# motor.net
KiCad netlist of a schematic drawn in Altium Designer
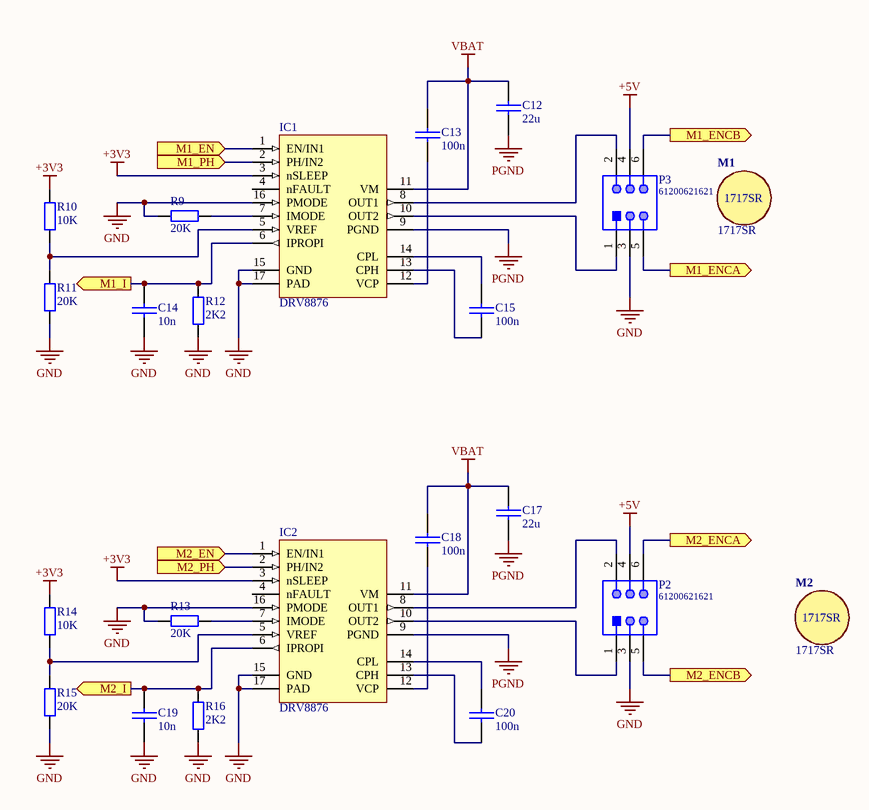
[diagram p0: motor.SchDoc]

(export (version "E")
  (design (tool "Eeschema 10.0.6"))
  (components
    (comp (ref "C12")
      (value "22u")
      (footprint "C0603_PASTE")
      (description "Multilayer Ceramic Capacitors MLCC - SMD 0603")
      (libsource (lib "Passives") (part "C-0603"))
    )
    (comp (ref "C13")
      (value "100n")
      (footprint "C0402-Paste")
      (description "Multilayer Ceramic Capacitors MLCC - SMD  0402")
      (libsource (lib "Passives") (part "C-0402"))
    )
    (comp (ref "C14")
      (value "10n")
      (footprint "C0402-Paste")
      (description "Multilayer Ceramic Capacitors MLCC - SMD  0402")
      (libsource (lib "Passives") (part "C-0402"))
    )
    (comp (ref "C15")
      (value "100n")
      (footprint "C0402-Paste")
      (description "Multilayer Ceramic Capacitors MLCC - SMD  0402")
      (libsource (lib "Passives") (part "C-0402"))
    )
    (comp (ref "C17")
      (value "22u")
      (footprint "C0603_PASTE")
      (description "Multilayer Ceramic Capacitors MLCC - SMD 0603")
      (libsource (lib "Passives") (part "C-0603"))
    )
    (comp (ref "C18")
      (value "100n")
      (footprint "C0402-Paste")
      (description "Multilayer Ceramic Capacitors MLCC - SMD  0402")
      (libsource (lib "Passives") (part "C-0402"))
    )
    (comp (ref "C19")
      (value "10n")
      (footprint "C0402-Paste")
      (description "Multilayer Ceramic Capacitors MLCC - SMD  0402")
      (libsource (lib "Passives") (part "C-0402"))
    )
    (comp (ref "C20")
      (value "100n")
      (footprint "C0402-Paste")
      (description "Multilayer Ceramic Capacitors MLCC - SMD  0402")
      (libsource (lib "Passives") (part "C-0402"))
    )
    (comp (ref "IC1")
      (value "DRV8876")
      (footprint "TSSOP-16H")
      (description "PWR MGMT MOTOR/FAN DRIVER")
      (libsource (lib "ICs") (part "DRV8876"))
    )
    (comp (ref "IC2")
      (value "DRV8876")
      (footprint "TSSOP-16H")
      (description "PWR MGMT MOTOR/FAN DRIVER")
      (libsource (lib "ICs") (part "DRV8876"))
    )
    (comp (ref "M1")
      (value "1717SR")
      (footprint "Motor")
      (libsource (lib "CMT-4023S-SMT-TR") (part "1717SR"))
    )
    (comp (ref "M2")
      (value "1717SR")
      (footprint "Motor")
      (libsource (lib "CMT-4023S-SMT-TR") (part "1717SR"))
    )
    (comp (ref "P2")
      (value "61200621621")
      (footprint "61200621621")
      (description "Male Box Header WR-BHD, THT, Vertical, pitch 2.54 mm, 6 pins")
      (fields (field (name "MANUFACTURER") "Wurth Elektronik") (field (name "PUBLISHER") "WurthElektronik"))
      (libsource (lib "Altium Content Vault") (part "WE-CN-2P-M-R6"))
    )
    (comp (ref "P3")
      (value "61200621621")
      (footprint "61200621621")
      (description "Male Box Header WR-BHD, THT, Vertical, pitch 2.54 mm, 6 pins")
      (fields (field (name "MANUFACTURER") "Wurth Elektronik") (field (name "PUBLISHER") "WurthElektronik"))
      (libsource (lib "Altium Content Vault") (part "WE-CN-2P-M-R6"))
    )
    (comp (ref "R9")
      (value "20K")
      (footprint "R0402-Paste")
      (description "RES SMD 0402")
      (libsource (lib "Passives") (part "R-0402"))
    )
    (comp (ref "R10")
      (value "10K")
      (footprint "R0402-Paste")
      (description "RES SMD 0402")
      (libsource (lib "Passives") (part "R-0402"))
    )
    (comp (ref "R11")
      (value "20K")
      (footprint "R0402-Paste")
      (description "RES SMD 0402")
      (libsource (lib "Passives") (part "R-0402"))
    )
    (comp (ref "R12")
      (value "2K2")
      (footprint "R0402-Paste")
      (description "RES SMD 0402")
      (libsource (lib "Passives") (part "R-0402"))
    )
    (comp (ref "R13")
      (value "20K")
      (footprint "R0402-Paste")
      (description "RES SMD 0402")
      (libsource (lib "Passives") (part "R-0402"))
    )
    (comp (ref "R14")
      (value "10K")
      (footprint "R0402-Paste")
      (description "RES SMD 0402")
      (libsource (lib "Passives") (part "R-0402"))
    )
    (comp (ref "R15")
      (value "20K")
      (footprint "R0402-Paste")
      (description "RES SMD 0402")
      (libsource (lib "Passives") (part "R-0402"))
    )
    (comp (ref "R16")
      (value "2K2")
      (footprint "R0402-Paste")
      (description "RES SMD 0402")
      (libsource (lib "Passives") (part "R-0402"))
    )
  )
  (nets
    (net (code "1") (name "+3V3") (class "Default")
      (node (ref "IC1") (pin "3") (pinfunction "nSLEEP_3") (pintype "input"))
      (node (ref "IC2") (pin "3") (pinfunction "nSLEEP_3") (pintype "input"))
      (node (ref "R10") (pin "2") (pinfunction "2_2") (pintype "passive"))
      (node (ref "R14") (pin "2") (pinfunction "2_2") (pintype "passive"))
    )
    (net (code "2") (name "+5V") (class "Default")
      (node (ref "P2") (pin "4") (pinfunction "4_4") (pintype "passive"))
      (node (ref "P3") (pin "4") (pinfunction "4_4") (pintype "passive"))
    )
    (net (code "3") (name "/M1_EN") (class "Default")
      (node (ref "IC1") (pin "1") (pinfunction "EN/IN1_1") (pintype "input"))
    )
    (net (code "4") (name "/M1_ENCA") (class "Default")
      (node (ref "P3") (pin "5") (pinfunction "5_5") (pintype "passive"))
    )
    (net (code "5") (name "/M1_ENCB") (class "Default")
      (node (ref "P3") (pin "6") (pinfunction "6_6") (pintype "passive"))
    )
    (net (code "6") (name "/M1_I") (class "Default")
      (node (ref "C14") (pin "1") (pintype "passive"))
      (node (ref "IC1") (pin "6") (pinfunction "IPROPI_6") (pintype "output"))
      (node (ref "R12") (pin "2") (pinfunction "2_2") (pintype "passive"))
    )
    (net (code "7") (name "/M1_PH") (class "Default")
      (node (ref "IC1") (pin "2") (pinfunction "PH/IN2_2") (pintype "input"))
    )
    (net (code "8") (name "/M2_EN") (class "Default")
      (node (ref "IC2") (pin "1") (pinfunction "EN/IN1_1") (pintype "input"))
    )
    (net (code "9") (name "/M2_ENCA") (class "Default")
      (node (ref "P2") (pin "6") (pinfunction "6_6") (pintype "passive"))
    )
    (net (code "10") (name "/M2_ENCB") (class "Default")
      (node (ref "P2") (pin "5") (pinfunction "5_5") (pintype "passive"))
    )
    (net (code "11") (name "/M2_I") (class "Default")
      (node (ref "C19") (pin "1") (pintype "passive"))
      (node (ref "IC2") (pin "6") (pinfunction "IPROPI_6") (pintype "output"))
      (node (ref "R16") (pin "2") (pinfunction "2_2") (pintype "passive"))
    )
    (net (code "12") (name "/M2_PH") (class "Default")
      (node (ref "IC2") (pin "2") (pinfunction "PH/IN2_2") (pintype "input"))
    )
    (net (code "13") (name "GND") (class "Default")
      (node (ref "C14") (pin "2") (pintype "passive"))
      (node (ref "C19") (pin "2") (pintype "passive"))
      (node (ref "IC1") (pin "15") (pinfunction "GND_15") (pintype "power_in"))
      (node (ref "IC1") (pin "16") (pinfunction "PMODE_16") (pintype "input"))
      (node (ref "IC1") (pin "17") (pinfunction "PAD_17") (pintype "power_in"))
      (node (ref "IC2") (pin "15") (pinfunction "GND_15") (pintype "power_in"))
      (node (ref "IC2") (pin "16") (pinfunction "PMODE_16") (pintype "input"))
      (node (ref "IC2") (pin "17") (pinfunction "PAD_17") (pintype "power_in"))
      (node (ref "P2") (pin "3") (pinfunction "3_3") (pintype "passive"))
      (node (ref "P3") (pin "3") (pinfunction "3_3") (pintype "passive"))
      (node (ref "R11") (pin "1") (pinfunction "1_1") (pintype "passive"))
      (node (ref "R12") (pin "1") (pinfunction "1_1") (pintype "passive"))
      (node (ref "R13") (pin "1") (pinfunction "1_1") (pintype "passive"))
      (node (ref "R15") (pin "1") (pinfunction "1_1") (pintype "passive"))
      (node (ref "R16") (pin "1") (pinfunction "1_1") (pintype "passive"))
      (node (ref "R9") (pin "1") (pinfunction "1_1") (pintype "passive"))
    )
    (net (code "14") (name "Net-(IC1-CPH)") (class "Default")
      (node (ref "C15") (pin "2") (pintype "passive"))
      (node (ref "IC1") (pin "13") (pinfunction "CPH_13") (pintype "power_in"))
    )
    (net (code "15") (name "Net-(IC1-CPL)") (class "Default")
      (node (ref "C15") (pin "1") (pintype "passive"))
      (node (ref "IC1") (pin "14") (pinfunction "CPL_14") (pintype "power_in"))
    )
    (net (code "16") (name "Net-(IC1-IMODE)") (class "Default")
      (node (ref "IC1") (pin "7") (pinfunction "IMODE_7") (pintype "input"))
      (node (ref "R9") (pin "2") (pinfunction "2_2") (pintype "passive"))
    )
    (net (code "17") (name "Net-(IC1-OUT1)") (class "Default")
      (node (ref "IC1") (pin "8") (pinfunction "OUT1_8") (pintype "output"))
      (node (ref "P3") (pin "2") (pinfunction "2_2") (pintype "passive"))
    )
    (net (code "18") (name "Net-(IC1-OUT2)") (class "Default")
      (node (ref "IC1") (pin "10") (pinfunction "OUT2_10") (pintype "output"))
      (node (ref "P3") (pin "1") (pinfunction "1_1") (pintype "passive"))
    )
    (net (code "19") (name "Net-(IC1-VCP)") (class "Default")
      (node (ref "C13") (pin "2") (pintype "passive"))
      (node (ref "IC1") (pin "12") (pinfunction "VCP_12") (pintype "power_in"))
    )
    (net (code "20") (name "Net-(IC1-VREF)") (class "Default")
      (node (ref "IC1") (pin "5") (pinfunction "VREF_5") (pintype "input"))
      (node (ref "R10") (pin "1") (pinfunction "1_1") (pintype "passive"))
      (node (ref "R11") (pin "2") (pinfunction "2_2") (pintype "passive"))
    )
    (net (code "21") (name "Net-(IC2-CPH)") (class "Default")
      (node (ref "C20") (pin "2") (pintype "passive"))
      (node (ref "IC2") (pin "13") (pinfunction "CPH_13") (pintype "power_in"))
    )
    (net (code "22") (name "Net-(IC2-CPL)") (class "Default")
      (node (ref "C20") (pin "1") (pintype "passive"))
      (node (ref "IC2") (pin "14") (pinfunction "CPL_14") (pintype "power_in"))
    )
    (net (code "23") (name "Net-(IC2-IMODE)") (class "Default")
      (node (ref "IC2") (pin "7") (pinfunction "IMODE_7") (pintype "input"))
      (node (ref "R13") (pin "2") (pinfunction "2_2") (pintype "passive"))
    )
    (net (code "24") (name "Net-(IC2-OUT1)") (class "Default")
      (node (ref "IC2") (pin "8") (pinfunction "OUT1_8") (pintype "output"))
      (node (ref "P2") (pin "2") (pinfunction "2_2") (pintype "passive"))
    )
    (net (code "25") (name "Net-(IC2-OUT2)") (class "Default")
      (node (ref "IC2") (pin "10") (pinfunction "OUT2_10") (pintype "output"))
      (node (ref "P2") (pin "1") (pinfunction "1_1") (pintype "passive"))
    )
    (net (code "26") (name "Net-(IC2-VCP)") (class "Default")
      (node (ref "C18") (pin "2") (pintype "passive"))
      (node (ref "IC2") (pin "12") (pinfunction "VCP_12") (pintype "power_in"))
    )
    (net (code "27") (name "Net-(IC2-VREF)") (class "Default")
      (node (ref "IC2") (pin "5") (pinfunction "VREF_5") (pintype "input"))
      (node (ref "R14") (pin "1") (pinfunction "1_1") (pintype "passive"))
      (node (ref "R15") (pin "2") (pinfunction "2_2") (pintype "passive"))
    )
    (net (code "28") (name "PGND") (class "Default")
      (node (ref "C12") (pin "2") (pintype "passive"))
      (node (ref "C17") (pin "2") (pintype "passive"))
      (node (ref "IC1") (pin "9") (pinfunction "PGND_9") (pintype "power_in"))
      (node (ref "IC2") (pin "9") (pinfunction "PGND_9") (pintype "power_in"))
    )
    (net (code "29") (name "VBAT") (class "Default")
      (node (ref "C12") (pin "1") (pintype "passive"))
      (node (ref "C13") (pin "1") (pintype "passive"))
      (node (ref "C17") (pin "1") (pintype "passive"))
      (node (ref "C18") (pin "1") (pintype "passive"))
      (node (ref "IC1") (pin "11") (pinfunction "VM_11") (pintype "power_in"))
      (node (ref "IC2") (pin "11") (pinfunction "VM_11") (pintype "power_in"))
    )
    (net (code "30") (name "unconnected-(IC1-nFAULT-Pad4)") (class "Default")
      (node (ref "IC1") (pin "4") (pinfunction "nFAULT_4") (pintype "open_collector"))
    )
    (net (code "31") (name "unconnected-(IC2-nFAULT-Pad4)") (class "Default")
      (node (ref "IC2") (pin "4") (pinfunction "nFAULT_4") (pintype "open_collector"))
    )
  )
)
